# SFPextensionSplit.net
KiCad netlist of a schematic drawn in Altium Designer
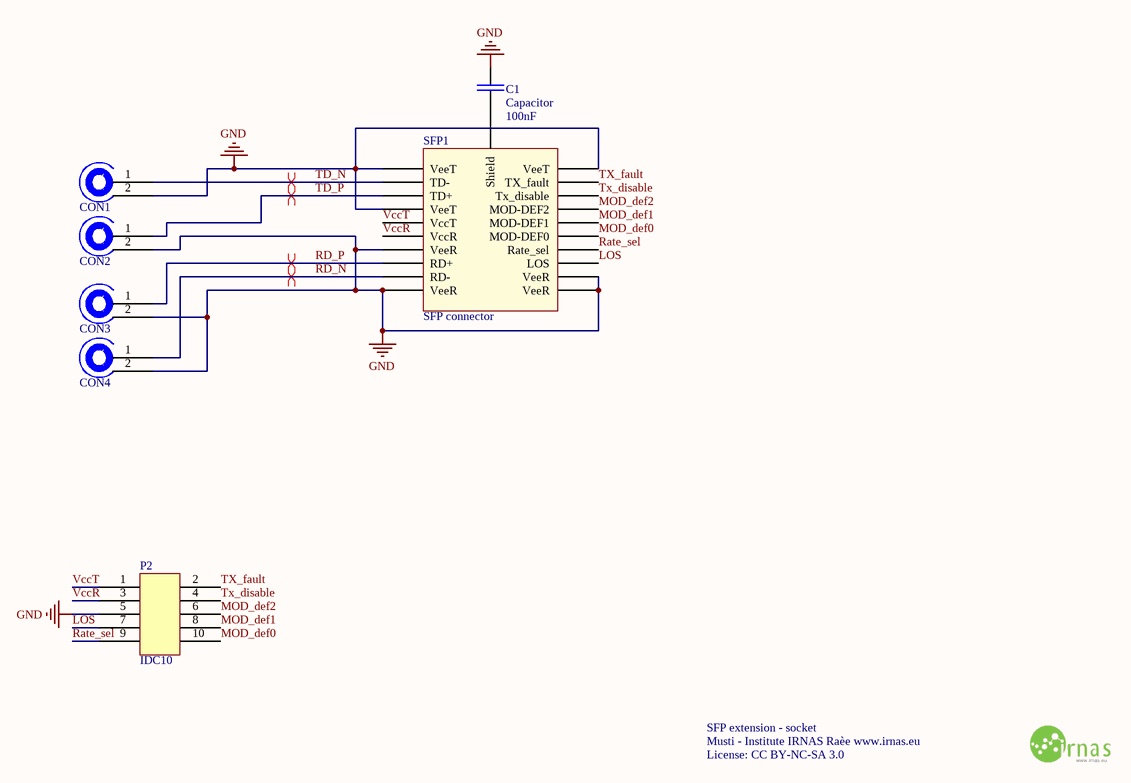
[diagram p0: SFPextensionSplit.SchDoc]

(export (version "E")
  (design (tool "Eeschema 10.0.6"))
  (components
    (comp (ref "C1")
      (value "Capacitor")
      (footprint "RESC2012X06N")
      (description "General capacitor")
      (fields (field (name "ALTIUM_VALUE") "100nF"))
      (libsource (lib "GeneralComponents") (part "Capacitor"))
    )
    (comp (ref "CON1")
      (value "Coaxial pcb connection")
      (footprint "SMD coaxial connector")
      (description "SMD PCB connector for coaxial cabel")
      (libsource (lib "PCB_connectors") (part "Coaxial pcb connection"))
    )
    (comp (ref "CON2")
      (value "Coaxial pcb connection")
      (footprint "SMD coaxial connector")
      (description "SMD PCB connector for coaxial cabel")
      (libsource (lib "PCB_connectors") (part "Coaxial pcb connection"))
    )
    (comp (ref "CON3")
      (value "Coaxial pcb connection")
      (footprint "SMD coaxial connector")
      (description "SMD PCB connector for coaxial cabel")
      (libsource (lib "PCB_connectors") (part "Coaxial pcb connection"))
    )
    (comp (ref "CON4")
      (value "Coaxial pcb connection")
      (footprint "SMD coaxial connector")
      (description "SMD PCB connector for coaxial cabel")
      (libsource (lib "PCB_connectors") (part "Coaxial pcb connection"))
    )
    (comp (ref "P2")
      (value "IDC10")
      (footprint "IDC10")
      (description "IDC 10pin")
      (libsource (lib "GeneralComponents") (part "IDC10"))
    )
    (comp (ref "SFP1")
      (value "SFP connector")
      (footprint "SFP receptacle")
      (libsource (lib "GeneralComponents") (part "SFP connector"))
    )
  )
  (nets
    (net (code "1") (name "/LOS") (class "Default")
      (node (ref "P2") (pin "7") (pinfunction "7_7") (pintype "passive"))
      (node (ref "SFP1") (pin "8") (pinfunction "LOS_8") (pintype "power_in"))
    )
    (net (code "2") (name "/MOD_def0") (class "Default")
      (node (ref "P2") (pin "10") (pinfunction "10_10") (pintype "passive"))
      (node (ref "SFP1") (pin "6") (pinfunction "MOD-DEF0_6") (pintype "power_in"))
    )
    (net (code "3") (name "/MOD_def1") (class "Default")
      (node (ref "P2") (pin "8") (pinfunction "8_8") (pintype "passive"))
      (node (ref "SFP1") (pin "5") (pinfunction "MOD-DEF1_5") (pintype "power_in"))
    )
    (net (code "4") (name "/MOD_def2") (class "Default")
      (node (ref "P2") (pin "6") (pinfunction "6_6") (pintype "passive"))
      (node (ref "SFP1") (pin "4") (pinfunction "MOD-DEF2_4") (pintype "power_in"))
    )
    (net (code "5") (name "/RD_N") (class "Default")
      (node (ref "CON4") (pin "1") (pinfunction "SIG_1") (pintype "passive"))
      (node (ref "SFP1") (pin "12") (pinfunction "RD-_12") (pintype "power_in"))
    )
    (net (code "6") (name "/RD_P") (class "Default")
      (node (ref "CON3") (pin "1") (pinfunction "SIG_1") (pintype "passive"))
      (node (ref "SFP1") (pin "13") (pinfunction "RD+_13") (pintype "power_in"))
    )
    (net (code "7") (name "/Rate_sel") (class "Default")
      (node (ref "P2") (pin "9") (pinfunction "9_9") (pintype "passive"))
      (node (ref "SFP1") (pin "7") (pinfunction "Rate_sel_7") (pintype "power_in"))
    )
    (net (code "8") (name "/TD_N") (class "Default")
      (node (ref "CON1") (pin "1") (pinfunction "SIG_1") (pintype "passive"))
      (node (ref "SFP1") (pin "19") (pinfunction "TD-_19") (pintype "power_in"))
    )
    (net (code "9") (name "/TD_P") (class "Default")
      (node (ref "CON2") (pin "1") (pinfunction "SIG_1") (pintype "passive"))
      (node (ref "SFP1") (pin "18") (pinfunction "TD+_18") (pintype "power_in"))
    )
    (net (code "10") (name "/TX_fault") (class "Default")
      (node (ref "P2") (pin "2") (pinfunction "2_2") (pintype "passive"))
      (node (ref "SFP1") (pin "2") (pinfunction "TX_fault_2") (pintype "power_in"))
    )
    (net (code "11") (name "/Tx_disable") (class "Default")
      (node (ref "P2") (pin "4") (pinfunction "4_4") (pintype "passive"))
      (node (ref "SFP1") (pin "3") (pinfunction "Tx_disable_3") (pintype "power_in"))
    )
    (net (code "12") (name "/VccR") (class "Default")
      (node (ref "P2") (pin "3") (pinfunction "3_3") (pintype "passive"))
      (node (ref "SFP1") (pin "15") (pinfunction "VccR_15") (pintype "power_in"))
    )
    (net (code "13") (name "/VccT") (class "Default")
      (node (ref "P2") (pin "1") (pinfunction "A_1") (pintype "passive"))
      (node (ref "SFP1") (pin "16") (pinfunction "VccT_16") (pintype "power_in"))
    )
    (net (code "14") (name "GND") (class "Default")
      (node (ref "C1") (pin "1") (pinfunction "1_1") (pintype "passive"))
      (node (ref "CON1") (pin "2") (pinfunction "GND_2") (pintype "passive"))
      (node (ref "CON2") (pin "2") (pinfunction "GND_2") (pintype "passive"))
      (node (ref "CON3") (pin "2") (pinfunction "GND_2") (pintype "passive"))
      (node (ref "CON4") (pin "2") (pinfunction "GND_2") (pintype "passive"))
      (node (ref "P2") (pin "5") (pinfunction "5_5") (pintype "passive"))
      (node (ref "SFP1") (pin "1") (pinfunction "VeeT_1") (pintype "power_in"))
      (node (ref "SFP1") (pin "10") (pinfunction "VeeR_10") (pintype "power_in"))
      (node (ref "SFP1") (pin "11") (pinfunction "VeeR_11") (pintype "power_in"))
      (node (ref "SFP1") (pin "14") (pinfunction "VeeR_14") (pintype "power_in"))
      (node (ref "SFP1") (pin "17") (pinfunction "VeeT_17") (pintype "power_in"))
      (node (ref "SFP1") (pin "20") (pinfunction "VeeT_20") (pintype "power_in"))
      (node (ref "SFP1") (pin "9") (pinfunction "VeeR_9") (pintype "power_in"))
    )
    (net (code "15") (name "Net-(SFP1-Shield)") (class "Default")
      (node (ref "C1") (pin "2") (pinfunction "2_2") (pintype "passive"))
      (node (ref "SFP1") (pin "21") (pinfunction "Shield_21") (pintype "power_in"))
    )
  )
)
